# ADC.net
KiCad netlist of a schematic drawn in EAGLE
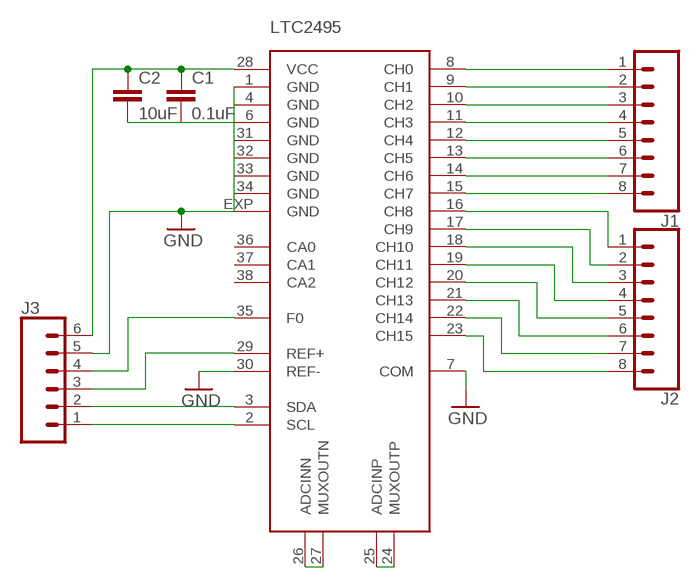
[diagram p0: schematic, sheet 1]

(export (version "E")
  (design (tool "Eeschema 10.0.6"))
  (components
    (comp (ref "C1")
      (value "0.1uF")
      (footprint "eagle-import:C0603")
      (libsource (lib "eagle-import") (part "C-EUC0603"))
    )
    (comp (ref "C2")
      (value "10uF")
      (footprint "eagle-import:C0805")
      (libsource (lib "eagle-import") (part "C-EUC0805"))
    )
    (comp (ref "J1")
      (value "CONN_08LONGPADS")
      (footprint "eagle-import:1X08_LONGPADS")
      (libsource (lib "eagle-import") (part "CONN_08LONGPADS"))
    )
    (comp (ref "J2")
      (value "CONN_08LONGPADS")
      (footprint "eagle-import:1X08_LONGPADS")
      (libsource (lib "eagle-import") (part "CONN_08LONGPADS"))
    )
    (comp (ref "J3")
      (value "CONN_06LONGPADS")
      (footprint "eagle-import:1X06_LONGPADS")
      (libsource (lib "eagle-import") (part "CONN_06LONGPADS"))
    )
    (comp (ref "U$1")
      (value "LTC2495")
      (footprint "eagle-import:QFN38-5X7")
      (libsource (lib "eagle-import") (part "LTC2495"))
    )
  )
  (nets
    (net (code "1") (name "GND") (class "Default")
      (node (ref "C1") (pin "2") (pinfunction "2_2") (pintype "passive"))
      (node (ref "C2") (pin "2") (pinfunction "2_2") (pintype "passive"))
      (node (ref "J3") (pin "5") (pinfunction "5_5") (pintype "passive"))
      (node (ref "U$1") (pin "1") (pinfunction "GND_1") (pintype "power_in"))
      (node (ref "U$1") (pin "30") (pinfunction "REF-_30") (pintype "input"))
      (node (ref "U$1") (pin "31") (pinfunction "GND_31") (pintype "power_in"))
      (node (ref "U$1") (pin "32") (pinfunction "GND_32") (pintype "power_in"))
      (node (ref "U$1") (pin "33") (pinfunction "GND_33") (pintype "power_in"))
      (node (ref "U$1") (pin "34") (pinfunction "GND_34") (pintype "power_in"))
      (node (ref "U$1") (pin "4") (pinfunction "GND_4") (pintype "power_in"))
      (node (ref "U$1") (pin "6") (pinfunction "GND_6") (pintype "power_in"))
      (node (ref "U$1") (pin "7") (pinfunction "COM_7") (pintype "input"))
      (node (ref "U$1") (pin "EXP") (pinfunction "GND_EXP") (pintype "power_in"))
    )
    (net (code "2") (name "Net-(U$1-ADCINN)") (class "Default")
      (node (ref "U$1") (pin "26") (pinfunction "ADCINN_26") (pintype "bidirectional"))
      (node (ref "U$1") (pin "27") (pinfunction "MUXOUTN_27") (pintype "bidirectional"))
    )
    (net (code "3") (name "Net-(U$1-ADCINP)") (class "Default")
      (node (ref "U$1") (pin "24") (pinfunction "MUXOUTP_24") (pintype "bidirectional"))
      (node (ref "U$1") (pin "25") (pinfunction "ADCINP_25") (pintype "bidirectional"))
    )
    (net (code "4") (name "Net-(U$1-CH0)") (class "Default")
      (node (ref "J1") (pin "1") (pinfunction "1_1") (pintype "passive"))
      (node (ref "U$1") (pin "8") (pinfunction "CH0_8") (pintype "input"))
    )
    (net (code "5") (name "Net-(U$1-CH1)") (class "Default")
      (node (ref "J1") (pin "2") (pinfunction "2_2") (pintype "passive"))
      (node (ref "U$1") (pin "9") (pinfunction "CH1_9") (pintype "input"))
    )
    (net (code "6") (name "Net-(U$1-CH2)") (class "Default")
      (node (ref "J1") (pin "3") (pinfunction "3_3") (pintype "passive"))
      (node (ref "U$1") (pin "10") (pinfunction "CH2_10") (pintype "input"))
    )
    (net (code "7") (name "Net-(U$1-CH3)") (class "Default")
      (node (ref "J1") (pin "4") (pinfunction "4_4") (pintype "passive"))
      (node (ref "U$1") (pin "11") (pinfunction "CH3_11") (pintype "input"))
    )
    (net (code "8") (name "Net-(U$1-CH4)") (class "Default")
      (node (ref "J1") (pin "5") (pinfunction "5_5") (pintype "passive"))
      (node (ref "U$1") (pin "12") (pinfunction "CH4_12") (pintype "input"))
    )
    (net (code "9") (name "Net-(U$1-CH5)") (class "Default")
      (node (ref "J1") (pin "6") (pinfunction "6_6") (pintype "passive"))
      (node (ref "U$1") (pin "13") (pinfunction "CH5_13") (pintype "input"))
    )
    (net (code "10") (name "Net-(U$1-CH6)") (class "Default")
      (node (ref "J1") (pin "7") (pinfunction "7_7") (pintype "passive"))
      (node (ref "U$1") (pin "14") (pinfunction "CH6_14") (pintype "input"))
    )
    (net (code "11") (name "Net-(U$1-CH7)") (class "Default")
      (node (ref "J1") (pin "8") (pinfunction "8_8") (pintype "passive"))
      (node (ref "U$1") (pin "15") (pinfunction "CH7_15") (pintype "input"))
    )
    (net (code "12") (name "Net-(U$1-CH8)") (class "Default")
      (node (ref "J2") (pin "1") (pinfunction "1_1") (pintype "passive"))
      (node (ref "U$1") (pin "16") (pinfunction "CH8_16") (pintype "input"))
    )
    (net (code "13") (name "Net-(U$1-CH9)") (class "Default")
      (node (ref "J2") (pin "2") (pinfunction "2_2") (pintype "passive"))
      (node (ref "U$1") (pin "17") (pinfunction "CH9_17") (pintype "input"))
    )
    (net (code "14") (name "Net-(U$1-CH10)") (class "Default")
      (node (ref "J2") (pin "3") (pinfunction "3_3") (pintype "passive"))
      (node (ref "U$1") (pin "18") (pinfunction "CH10_18") (pintype "input"))
    )
    (net (code "15") (name "Net-(U$1-CH11)") (class "Default")
      (node (ref "J2") (pin "4") (pinfunction "4_4") (pintype "passive"))
      (node (ref "U$1") (pin "19") (pinfunction "CH11_19") (pintype "input"))
    )
    (net (code "16") (name "Net-(U$1-CH12)") (class "Default")
      (node (ref "J2") (pin "5") (pinfunction "5_5") (pintype "passive"))
      (node (ref "U$1") (pin "20") (pinfunction "CH12_20") (pintype "input"))
    )
    (net (code "17") (name "Net-(U$1-CH13)") (class "Default")
      (node (ref "J2") (pin "6") (pinfunction "6_6") (pintype "passive"))
      (node (ref "U$1") (pin "21") (pinfunction "CH13_21") (pintype "input"))
    )
    (net (code "18") (name "Net-(U$1-CH14)") (class "Default")
      (node (ref "J2") (pin "7") (pinfunction "7_7") (pintype "passive"))
      (node (ref "U$1") (pin "22") (pinfunction "CH14_22") (pintype "input"))
    )
    (net (code "19") (name "Net-(U$1-CH15)") (class "Default")
      (node (ref "J2") (pin "8") (pinfunction "8_8") (pintype "passive"))
      (node (ref "U$1") (pin "23") (pinfunction "CH15_23") (pintype "input"))
    )
    (net (code "20") (name "Net-(U$1-F0)") (class "Default")
      (node (ref "J3") (pin "4") (pinfunction "4_4") (pintype "passive"))
      (node (ref "U$1") (pin "35") (pinfunction "F0_35") (pintype "input"))
    )
    (net (code "21") (name "Net-(U$1-REF+)") (class "Default")
      (node (ref "J3") (pin "3") (pinfunction "3_3") (pintype "passive"))
      (node (ref "U$1") (pin "29") (pinfunction "REF+_29") (pintype "input"))
    )
    (net (code "22") (name "Net-(U$1-SCL)") (class "Default")
      (node (ref "J3") (pin "1") (pinfunction "1_1") (pintype "passive"))
      (node (ref "U$1") (pin "2") (pinfunction "SCL_2") (pintype "bidirectional"))
    )
    (net (code "23") (name "Net-(U$1-SDA)") (class "Default")
      (node (ref "J3") (pin "2") (pinfunction "2_2") (pintype "passive"))
      (node (ref "U$1") (pin "3") (pinfunction "SDA_3") (pintype "bidirectional"))
    )
    (net (code "24") (name "Net-(U$1-VCC)") (class "Default")
      (node (ref "C1") (pin "1") (pinfunction "1_1") (pintype "passive"))
      (node (ref "C2") (pin "1") (pinfunction "1_1") (pintype "passive"))
      (node (ref "J3") (pin "6") (pinfunction "6_6") (pintype "passive"))
      (node (ref "U$1") (pin "28") (pinfunction "VCC_28") (pintype "power_in"))
    )
    (net (code "25") (name "unconnected-(U$1-CA0-Pad36)") (class "Default")
      (node (ref "U$1") (pin "36") (pinfunction "CA0_36") (pintype "input"))
    )
    (net (code "26") (name "unconnected-(U$1-CA1-Pad37)") (class "Default")
      (node (ref "U$1") (pin "37") (pinfunction "CA1_37") (pintype "input"))
    )
    (net (code "27") (name "unconnected-(U$1-CA2-Pad38)") (class "Default")
      (node (ref "U$1") (pin "38") (pinfunction "CA2_38") (pintype "input"))
    )
  )
)
